# FLASH.net
KiCad netlist of a schematic drawn in Altium Designer
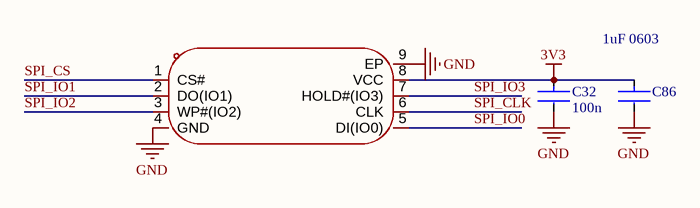
[diagram p0: FLASH.SchDoc]

(export (version "E")
  (design (tool "Eeschema 10.0.6"))
  (components
    (comp (ref "C32")
      (value "100n")
      (footprint "CAP_0402")
      (description "C307331")
      (fields (field (name "TOLERANCE") "10%"))
      (libsource (lib "LEAKCAM") (part "CMP-03422-001116-1"))
    )
    (comp (ref "C86")
      (value "1uF 0603")
      (footprint "FP-GRM188-0_15-MFG")
      (description "C15849")
      (fields (field (name "TOLERANCE") "20%"))
      (libsource (lib "LEAKCAM") (part "CMP-06035-003612-1"))
    )
    (comp (ref "U16")
      (value "w25n02kvzeir")
      (footprint "w25n02")
      (description "C17626844")
      (fields (field (name "MANUFACTURER") "Winbond(华邦)") (field (name "MANUFACTURERPART") "W25N02KVZEIR"))
      (libsource (lib "LEAKCAM") (part "w25n02kvzeir"))
    )
  )
  (nets
    (net (code "1") (name "/SPI_CLK") (class "Default")
      (node (ref "U16") (pin "6") (pinfunction "CLK_6") (pintype "passive"))
    )
    (net (code "2") (name "/SPI_CS") (class "Default")
      (node (ref "U16") (pin "1") (pinfunction "CS#_1") (pintype "passive"))
    )
    (net (code "3") (name "/SPI_IO0") (class "Default")
      (node (ref "U16") (pin "5") (pinfunction "DI(IO0)_5") (pintype "passive"))
    )
    (net (code "4") (name "/SPI_IO1") (class "Default")
      (node (ref "U16") (pin "2") (pinfunction "DO(IO1)_2") (pintype "passive"))
    )
    (net (code "5") (name "/SPI_IO2") (class "Default")
      (node (ref "U16") (pin "3") (pinfunction "WP#(IO2)_3") (pintype "passive"))
    )
    (net (code "6") (name "/SPI_IO3") (class "Default")
      (node (ref "U16") (pin "7") (pinfunction "HOLD#(IO3)_7") (pintype "passive"))
    )
    (net (code "7") (name "3V3") (class "Default")
      (node (ref "C32") (pin "1") (pinfunction "1_1") (pintype "passive"))
      (node (ref "C86") (pin "1") (pinfunction "1_1") (pintype "passive"))
      (node (ref "U16") (pin "8") (pinfunction "VCC_8") (pintype "passive"))
    )
    (net (code "8") (name "GND") (class "Default")
      (node (ref "C32") (pin "2") (pinfunction "2_2") (pintype "passive"))
      (node (ref "C86") (pin "2") (pinfunction "2_2") (pintype "passive"))
      (node (ref "U16") (pin "4") (pinfunction "GND_4") (pintype "passive"))
      (node (ref "U16") (pin "9") (pinfunction "EP_9") (pintype "passive"))
    )
  )
)
